# Zigbee32Bridge.net
KiCad netlist of a schematic drawn in Altium Designer
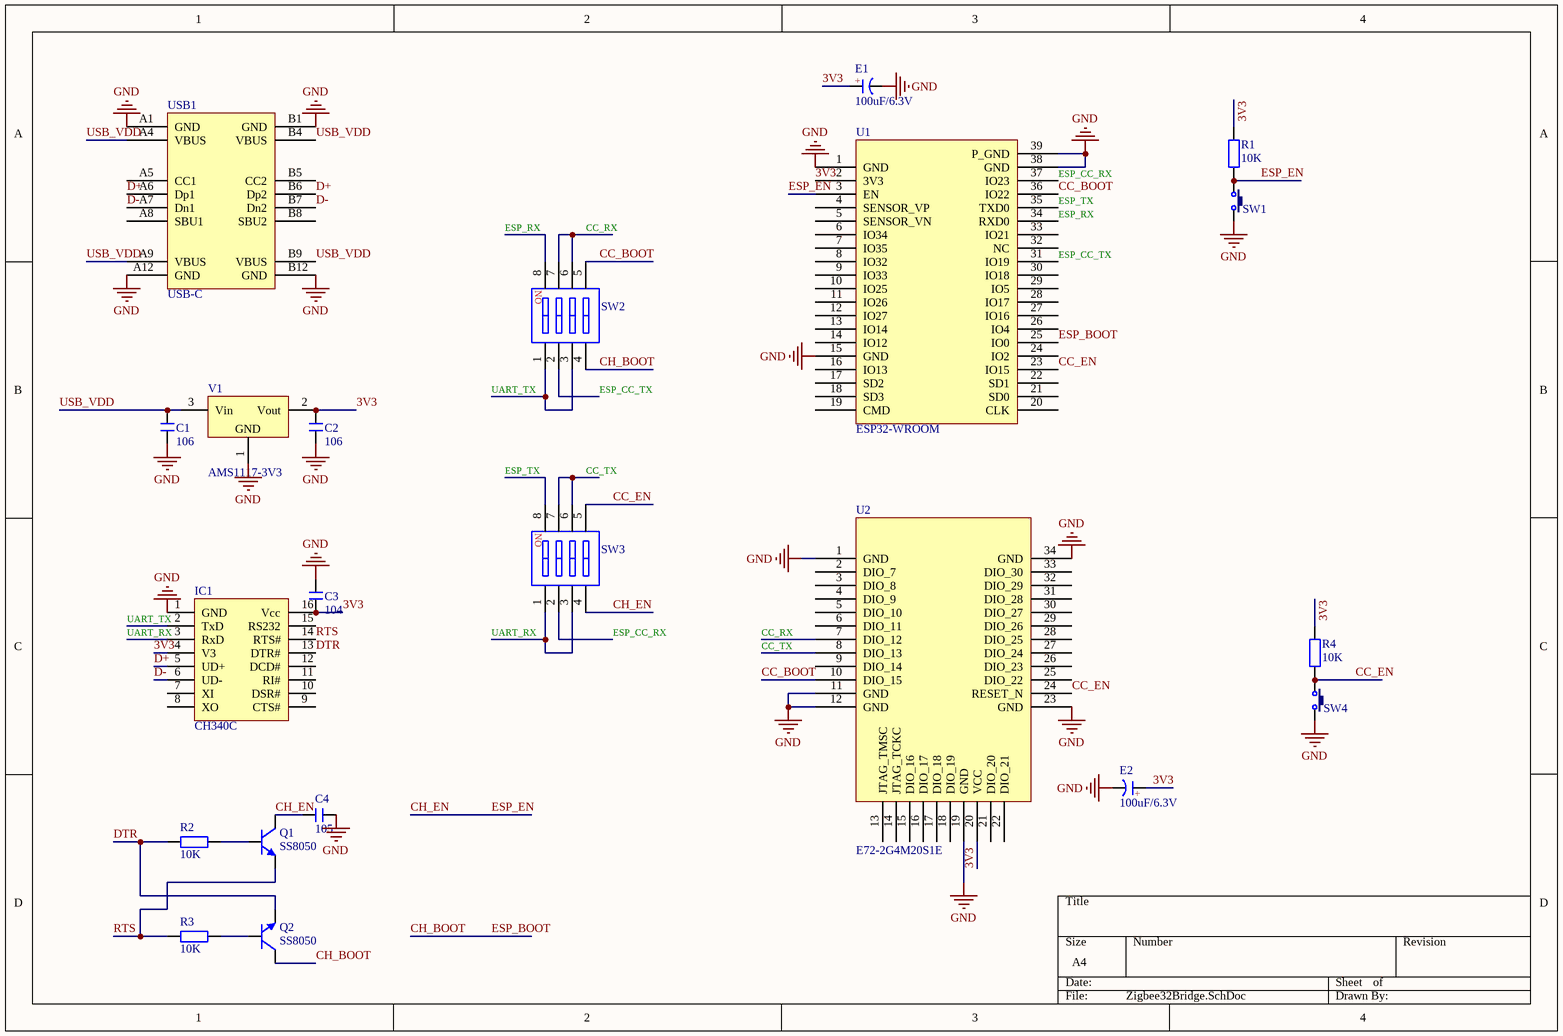
[diagram p0: Zigbee32Bridge.SchDoc]

(export (version "E")
  (design (tool "Eeschema 10.0.6"))
  (components
    (comp (ref "C1")
      (value "106")
      (footprint "C 0603_L")
      (description "无极性贴片电容")
      (fields (field (name "版权归属") "源创客"))
      (libsource (lib "3.1   - 电阻-电容-电感") (part "C"))
    )
    (comp (ref "C2")
      (value "106")
      (footprint "C 0603_L")
      (description "无极性贴片电容")
      (fields (field (name "版权归属") "源创客"))
      (libsource (lib "3.1   - 电阻-电容-电感") (part "C"))
    )
    (comp (ref "C3")
      (value "104")
      (footprint "C 0603_L")
      (description "无极性贴片电容")
      (fields (field (name "版权归属") "源创客"))
      (libsource (lib "3.1   - 电阻-电容-电感") (part "C"))
    )
    (comp (ref "C4")
      (value "105")
      (footprint "C 0603_L")
      (description "无极性贴片电容")
      (fields (field (name "版权归属") "源创客"))
      (libsource (lib "3.1   - 电阻-电容-电感") (part "C"))
    )
    (comp (ref "E1")
      (value "100uF/6.3V")
      (footprint "CD A(3216)")
      (description "贴片钽电容")
      (fields (field (name "版权归属") "源创客"))
      (libsource (lib "3.1   - 电阻-电容-电感") (part "C-CD"))
    )
    (comp (ref "E2")
      (value "100uF/6.3V")
      (footprint "CD A(3216)")
      (description "贴片钽电容")
      (fields (field (name "版权归属") "源创客"))
      (libsource (lib "3.1   - 电阻-电容-电感") (part "C-CD"))
    )
    (comp (ref "IC1")
      (value "CH340C")
      (footprint "SOP16_N")
      (description "串口转USB")
      (fields (field (name "版权归属") "源创客"))
      (libsource (lib "1.1   - IC芯片") (part "CH340G"))
    )
    (comp (ref "Q1")
      (value "SS8050")
      (footprint "SOT23-3N")
      (description "高频放大-NPN型")
      (fields (field (name "版权归属") "源创客"))
      (libsource (lib "6.2   - 三极管") (part "8050-SMD"))
    )
    (comp (ref "Q2")
      (value "SS8050")
      (footprint "SOT23-3N")
      (description "高频放大-NPN型")
      (fields (field (name "版权归属") "源创客"))
      (libsource (lib "6.2   - 三极管") (part "8050-SMD"))
    )
    (comp (ref "R1")
      (value "10K")
      (footprint "R 0603_L")
      (description "贴片电阻")
      (fields (field (name "版权归属") "源创客"))
      (libsource (lib "3.1   - 电阻-电容-电感") (part "R"))
    )
    (comp (ref "R2")
      (value "10K")
      (footprint "R 0603_L")
      (description "贴片电阻")
      (fields (field (name "版权归属") "源创客"))
      (libsource (lib "3.1   - 电阻-电容-电感") (part "R"))
    )
    (comp (ref "R3")
      (value "10K")
      (footprint "R 0603_L")
      (description "贴片电阻")
      (fields (field (name "版权归属") "源创客"))
      (libsource (lib "3.1   - 电阻-电容-电感") (part "R"))
    )
    (comp (ref "R4")
      (value "10K")
      (footprint "R 0603_L")
      (description "贴片电阻")
      (fields (field (name "版权归属") "源创客"))
      (libsource (lib "3.1   - 电阻-电容-电感") (part "R"))
    )
    (comp (ref "SW1")
      (value "3x4x5")
      (footprint "TS3x4x2")
      (description "3x4轻触开关")
      (fields (field (name "版权归属") "源创客"))
      (libsource (lib "5.1   - 按键-开关") (part "TS 3x4"))
    )
    (comp (ref "SW2")
      (value "CSW-4P")
      (footprint "CSW1.27 SMD-4P")
      (description "4路编码开关")
      (fields (field (name "版权归属") "源创客"))
      (libsource (lib "5.1   - 按键-开关") (part "CSW-4P"))
    )
    (comp (ref "SW3")
      (value "CSW-4P")
      (footprint "CSW1.27 SMD-4P")
      (description "4路编码开关")
      (fields (field (name "版权归属") "源创客"))
      (libsource (lib "5.1   - 按键-开关") (part "CSW-4P"))
    )
    (comp (ref "SW4")
      (value "3x4x5")
      (footprint "TS3x4x2")
      (description "3x4轻触开关")
      (fields (field (name "版权归属") "源创客"))
      (libsource (lib "5.1   - 按键-开关") (part "TS 3x4"))
    )
    (comp (ref "U1")
      (value "ESP32-WROOM")
      (footprint "ESP32-WROOM")
      (libsource (lib "15.1 - 未分类器件") (part "ESP32-WROOM"))
    )
    (comp (ref "U2")
      (value "E72-2G4M20S1E")
      (footprint "RF-BM-2652P2")
      (libsource (lib "CustomLib") (part "E72-2G4M20S1E"))
    )
    (comp (ref "USB1")
      (value "USB-C")
      (footprint "USB Type-C-16Pin_A")
      (description "USB-C型母接口")
      (fields (field (name "版权归属") "源创客"))
      (libsource (lib "4.1   - 接口类") (part "USB-C-16P"))
    )
    (comp (ref "V1")
      (value "AMS1117-3V3")
      (footprint "SOT223_N")
      (description "三端稳压芯片")
      (fields (field (name "版权归属") "源创客"))
      (libsource (lib "1.3   - 电源类芯片") (part "AMS1117"))
    )
  )
  (nets
    (net (code "1") (name "/3V3") (class "Default")
      (node (ref "C2") (pin "2") (pinfunction "2_2") (pintype "passive"))
      (node (ref "C3") (pin "2") (pinfunction "2_2") (pintype "passive"))
      (node (ref "E1") (pin "1") (pinfunction "A_1") (pintype "passive"))
      (node (ref "E2") (pin "1") (pinfunction "A_1") (pintype "passive"))
      (node (ref "IC1") (pin "16") (pinfunction "Vcc_16") (pintype "passive"))
      (node (ref "IC1") (pin "4") (pinfunction "V3_4") (pintype "passive"))
      (node (ref "R1") (pin "2") (pinfunction "2_2") (pintype "passive"))
      (node (ref "R4") (pin "2") (pinfunction "2_2") (pintype "passive"))
      (node (ref "U1") (pin "2") (pinfunction "3V3_2") (pintype "passive"))
      (node (ref "U2") (pin "20") (pinfunction "VCC_20") (pintype "passive"))
      (node (ref "V1") (pin "2") (pinfunction "Vout_2") (pintype "passive"))
    )
    (net (code "2") (name "/CC_BOOT") (class "Default")
      (node (ref "SW2") (pin "5") (pinfunction "5_5") (pintype "passive"))
      (node (ref "U1") (pin "36") (pinfunction "IO22_36") (pintype "passive"))
      (node (ref "U2") (pin "10") (pinfunction "DIO_15_10") (pintype "passive"))
    )
    (net (code "3") (name "/CC_EN") (class "Default")
      (node (ref "R4") (pin "1") (pinfunction "1_1") (pintype "passive"))
      (node (ref "SW3") (pin "5") (pinfunction "5_5") (pintype "passive"))
      (node (ref "SW4") (pin "1") (pinfunction "1_1") (pintype "passive"))
      (node (ref "U1") (pin "23") (pinfunction "IO15_23") (pintype "passive"))
      (node (ref "U2") (pin "24") (pinfunction "RESET_N_24") (pintype "passive"))
    )
    (net (code "4") (name "/CC_RX") (class "Default")
      (node (ref "SW2") (pin "6") (pinfunction "6_6") (pintype "passive"))
      (node (ref "SW2") (pin "7") (pinfunction "7_7") (pintype "passive"))
      (node (ref "U2") (pin "7") (pinfunction "DIO_12_7") (pintype "passive"))
    )
    (net (code "5") (name "/CC_TX") (class "Default")
      (node (ref "SW3") (pin "6") (pinfunction "6_6") (pintype "passive"))
      (node (ref "SW3") (pin "7") (pinfunction "7_7") (pintype "passive"))
      (node (ref "U2") (pin "8") (pinfunction "DIO_13_8") (pintype "passive"))
    )
    (net (code "6") (name "/CH_BOOT") (class "Default")
      (node (ref "Q2") (pin "3") (pinfunction "C_3") (pintype "passive"))
      (node (ref "SW2") (pin "4") (pinfunction "4_4") (pintype "passive"))
      (node (ref "U1") (pin "25") (pinfunction "IO0_25") (pintype "passive"))
    )
    (net (code "7") (name "/CH_EN") (class "Default")
      (node (ref "C4") (pin "2") (pinfunction "2_2") (pintype "passive"))
      (node (ref "Q1") (pin "3") (pinfunction "C_3") (pintype "passive"))
      (node (ref "R1") (pin "1") (pinfunction "1_1") (pintype "passive"))
      (node (ref "SW1") (pin "1") (pinfunction "1_1") (pintype "passive"))
      (node (ref "SW3") (pin "4") (pinfunction "4_4") (pintype "passive"))
      (node (ref "U1") (pin "3") (pinfunction "EN_3") (pintype "passive"))
    )
    (net (code "8") (name "/D+") (class "Default")
      (node (ref "IC1") (pin "5") (pinfunction "UD+_5") (pintype "passive"))
      (node (ref "USB1") (pin "A6") (pinfunction "Dp1_A6") (pintype "passive"))
      (node (ref "USB1") (pin "B6") (pinfunction "Dp2_B6") (pintype "passive"))
    )
    (net (code "9") (name "/D-") (class "Default")
      (node (ref "IC1") (pin "6") (pinfunction "UD-_6") (pintype "passive"))
      (node (ref "USB1") (pin "A7") (pinfunction "Dn1_A7") (pintype "passive"))
      (node (ref "USB1") (pin "B7") (pinfunction "Dn2_B7") (pintype "passive"))
    )
    (net (code "10") (name "/DTR") (class "Default")
      (node (ref "IC1") (pin "13") (pinfunction "DTR#_13") (pintype "passive"))
      (node (ref "Q2") (pin "2") (pinfunction "E_2") (pintype "passive"))
      (node (ref "R2") (pin "1") (pinfunction "1_1") (pintype "passive"))
    )
    (net (code "11") (name "/ESP_CC_RX") (class "Default")
      (node (ref "SW3") (pin "2") (pinfunction "2_2") (pintype "passive"))
      (node (ref "U1") (pin "37") (pinfunction "IO23_37") (pintype "passive"))
    )
    (net (code "12") (name "/ESP_CC_TX") (class "Default")
      (node (ref "SW2") (pin "2") (pinfunction "2_2") (pintype "passive"))
      (node (ref "U1") (pin "31") (pinfunction "IO19_31") (pintype "passive"))
    )
    (net (code "13") (name "/ESP_RX") (class "Default")
      (node (ref "SW2") (pin "8") (pinfunction "8_8") (pintype "passive"))
      (node (ref "U1") (pin "34") (pinfunction "RXD0_34") (pintype "passive"))
    )
    (net (code "14") (name "/ESP_TX") (class "Default")
      (node (ref "SW3") (pin "8") (pinfunction "8_8") (pintype "passive"))
      (node (ref "U1") (pin "35") (pinfunction "TXD0_35") (pintype "passive"))
    )
    (net (code "15") (name "/RTS") (class "Default")
      (node (ref "IC1") (pin "14") (pinfunction "RTS#_14") (pintype "passive"))
      (node (ref "Q1") (pin "2") (pinfunction "E_2") (pintype "passive"))
      (node (ref "R3") (pin "1") (pinfunction "1_1") (pintype "passive"))
    )
    (net (code "16") (name "/UART_RX") (class "Default")
      (node (ref "IC1") (pin "3") (pinfunction "RxD_3") (pintype "passive"))
      (node (ref "SW3") (pin "1") (pinfunction "1_1") (pintype "passive"))
      (node (ref "SW3") (pin "3") (pinfunction "3_3") (pintype "passive"))
    )
    (net (code "17") (name "/UART_TX") (class "Default")
      (node (ref "IC1") (pin "2") (pinfunction "TxD_2") (pintype "passive"))
      (node (ref "SW2") (pin "1") (pinfunction "1_1") (pintype "passive"))
      (node (ref "SW2") (pin "3") (pinfunction "3_3") (pintype "passive"))
    )
    (net (code "18") (name "/USB_VDD") (class "Default")
      (node (ref "C1") (pin "2") (pinfunction "2_2") (pintype "passive"))
      (node (ref "USB1") (pin "A4") (pinfunction "VBUS_A4") (pintype "passive"))
      (node (ref "USB1") (pin "A9") (pinfunction "VBUS_A9") (pintype "passive"))
      (node (ref "USB1") (pin "B4") (pinfunction "VBUS_B4") (pintype "passive"))
      (node (ref "USB1") (pin "B9") (pinfunction "VBUS_B9") (pintype "passive"))
      (node (ref "V1") (pin "3") (pinfunction "Vin_3") (pintype "passive"))
    )
    (net (code "19") (name "GND") (class "Default")
      (node (ref "C1") (pin "1") (pinfunction "1_1") (pintype "passive"))
      (node (ref "C2") (pin "1") (pinfunction "1_1") (pintype "passive"))
      (node (ref "C3") (pin "1") (pinfunction "1_1") (pintype "passive"))
      (node (ref "C4") (pin "1") (pinfunction "1_1") (pintype "passive"))
      (node (ref "E1") (pin "2") (pinfunction "K_2") (pintype "passive"))
      (node (ref "E2") (pin "2") (pinfunction "K_2") (pintype "passive"))
      (node (ref "IC1") (pin "1") (pinfunction "GND_1") (pintype "passive"))
      (node (ref "SW1") (pin "2") (pinfunction "2_2") (pintype "passive"))
      (node (ref "SW4") (pin "2") (pinfunction "2_2") (pintype "passive"))
      (node (ref "U1") (pin "1") (pinfunction "GND_1") (pintype "passive"))
      (node (ref "U1") (pin "15") (pinfunction "GND_15") (pintype "passive"))
      (node (ref "U1") (pin "38") (pinfunction "GND_38") (pintype "passive"))
      (node (ref "U1") (pin "39") (pinfunction "P_GND_39") (pintype "passive"))
      (node (ref "U2") (pin "1") (pinfunction "GND_1") (pintype "passive"))
      (node (ref "U2") (pin "11") (pinfunction "GND_11") (pintype "passive"))
      (node (ref "U2") (pin "12") (pinfunction "GND_12") (pintype "passive"))
      (node (ref "U2") (pin "19") (pinfunction "GND_19") (pintype "passive"))
      (node (ref "U2") (pin "23") (pinfunction "GND_23") (pintype "passive"))
      (node (ref "U2") (pin "34") (pinfunction "GND_34") (pintype "passive"))
      (node (ref "USB1") (pin "A1") (pinfunction "GND_A1") (pintype "passive"))
      (node (ref "USB1") (pin "A12") (pinfunction "GND_A12") (pintype "passive"))
      (node (ref "USB1") (pin "B1") (pinfunction "GND_B1") (pintype "passive"))
      (node (ref "USB1") (pin "B12") (pinfunction "GND_B12") (pintype "passive"))
      (node (ref "V1") (pin "1") (pinfunction "GND_1") (pintype "passive"))
    )
    (net (code "20") (name "Net-(Q1-B)") (class "Default")
      (node (ref "Q1") (pin "1") (pinfunction "B_1") (pintype "passive"))
      (node (ref "R2") (pin "2") (pinfunction "2_2") (pintype "passive"))
    )
    (net (code "21") (name "Net-(Q2-B)") (class "Default")
      (node (ref "Q2") (pin "1") (pinfunction "B_1") (pintype "passive"))
      (node (ref "R3") (pin "2") (pinfunction "2_2") (pintype "passive"))
    )
    (net (code "22") (name "unconnected-(IC1-CTS#-Pad9)") (class "Default")
      (node (ref "IC1") (pin "9") (pinfunction "CTS#_9") (pintype "passive"))
    )
    (net (code "23") (name "unconnected-(IC1-DCD#-Pad12)") (class "Default")
      (node (ref "IC1") (pin "12") (pinfunction "DCD#_12") (pintype "passive"))
    )
    (net (code "24") (name "unconnected-(IC1-DSR#-Pad10)") (class "Default")
      (node (ref "IC1") (pin "10") (pinfunction "DSR#_10") (pintype "passive"))
    )
    (net (code "25") (name "unconnected-(IC1-RI#-Pad11)") (class "Default")
      (node (ref "IC1") (pin "11") (pinfunction "RI#_11") (pintype "passive"))
    )
    (net (code "26") (name "unconnected-(IC1-RS232-Pad15)") (class "Default")
      (node (ref "IC1") (pin "15") (pinfunction "RS232_15") (pintype "passive"))
    )
    (net (code "27") (name "unconnected-(IC1-XI-Pad7)") (class "Default")
      (node (ref "IC1") (pin "7") (pinfunction "XI_7") (pintype "passive"))
    )
    (net (code "28") (name "unconnected-(IC1-XO-Pad8)") (class "Default")
      (node (ref "IC1") (pin "8") (pinfunction "XO_8") (pintype "passive"))
    )
    (net (code "29") (name "unconnected-(U1-CLK-Pad20)") (class "Default")
      (node (ref "U1") (pin "20") (pinfunction "CLK_20") (pintype "passive"))
    )
    (net (code "30") (name "unconnected-(U1-CMD-Pad19)") (class "Default")
      (node (ref "U1") (pin "19") (pinfunction "CMD_19") (pintype "passive"))
    )
    (net (code "31") (name "unconnected-(U1-IO2-Pad24)") (class "Default")
      (node (ref "U1") (pin "24") (pinfunction "IO2_24") (pintype "passive"))
    )
    (net (code "32") (name "unconnected-(U1-IO4-Pad26)") (class "Default")
      (node (ref "U1") (pin "26") (pinfunction "IO4_26") (pintype "passive"))
    )
    (net (code "33") (name "unconnected-(U1-IO5-Pad29)") (class "Default")
      (node (ref "U1") (pin "29") (pinfunction "IO5_29") (pintype "passive"))
    )
    (net (code "34") (name "unconnected-(U1-IO12-Pad14)") (class "Default")
      (node (ref "U1") (pin "14") (pinfunction "IO12_14") (pintype "passive"))
    )
    (net (code "35") (name "unconnected-(U1-IO13-Pad16)") (class "Default")
      (node (ref "U1") (pin "16") (pinfunction "IO13_16") (pintype "passive"))
    )
    (net (code "36") (name "unconnected-(U1-IO14-Pad13)") (class "Default")
      (node (ref "U1") (pin "13") (pinfunction "IO14_13") (pintype "passive"))
    )
    (net (code "37") (name "unconnected-(U1-IO16-Pad27)") (class "Default")
      (node (ref "U1") (pin "27") (pinfunction "IO16_27") (pintype "passive"))
    )
    (net (code "38") (name "unconnected-(U1-IO17-Pad28)") (class "Default")
      (node (ref "U1") (pin "28") (pinfunction "IO17_28") (pintype "passive"))
    )
    (net (code "39") (name "unconnected-(U1-IO18-Pad30)") (class "Default")
      (node (ref "U1") (pin "30") (pinfunction "IO18_30") (pintype "passive"))
    )
    (net (code "40") (name "unconnected-(U1-IO21-Pad33)") (class "Default")
      (node (ref "U1") (pin "33") (pinfunction "IO21_33") (pintype "passive"))
    )
    (net (code "41") (name "unconnected-(U1-IO25-Pad10)") (class "Default")
      (node (ref "U1") (pin "10") (pinfunction "IO25_10") (pintype "passive"))
    )
    (net (code "42") (name "unconnected-(U1-IO26-Pad11)") (class "Default")
      (node (ref "U1") (pin "11") (pinfunction "IO26_11") (pintype "passive"))
    )
    (net (code "43") (name "unconnected-(U1-IO27-Pad12)") (class "Default")
      (node (ref "U1") (pin "12") (pinfunction "IO27_12") (pintype "passive"))
    )
    (net (code "44") (name "unconnected-(U1-IO32-Pad8)") (class "Default")
      (node (ref "U1") (pin "8") (pinfunction "IO32_8") (pintype "passive"))
    )
    (net (code "45") (name "unconnected-(U1-IO33-Pad9)") (class "Default")
      (node (ref "U1") (pin "9") (pinfunction "IO33_9") (pintype "passive"))
    )
    (net (code "46") (name "unconnected-(U1-IO34-Pad6)") (class "Default")
      (node (ref "U1") (pin "6") (pinfunction "IO34_6") (pintype "passive"))
    )
    (net (code "47") (name "unconnected-(U1-IO35-Pad7)") (class "Default")
      (node (ref "U1") (pin "7") (pinfunction "IO35_7") (pintype "passive"))
    )
    (net (code "48") (name "unconnected-(U1-NC-Pad32)") (class "Default")
      (node (ref "U1") (pin "32") (pinfunction "NC_32") (pintype "passive"))
    )
    (net (code "49") (name "unconnected-(U1-SD0-Pad21)") (class "Default")
      (node (ref "U1") (pin "21") (pinfunction "SD0_21") (pintype "passive"))
    )
    (net (code "50") (name "unconnected-(U1-SD1-Pad22)") (class "Default")
      (node (ref "U1") (pin "22") (pinfunction "SD1_22") (pintype "passive"))
    )
    (net (code "51") (name "unconnected-(U1-SD2-Pad17)") (class "Default")
      (node (ref "U1") (pin "17") (pinfunction "SD2_17") (pintype "passive"))
    )
    (net (code "52") (name "unconnected-(U1-SD3-Pad18)") (class "Default")
      (node (ref "U1") (pin "18") (pinfunction "SD3_18") (pintype "passive"))
    )
    (net (code "53") (name "unconnected-(U1-SENSOR_VN-Pad5)") (class "Default")
      (node (ref "U1") (pin "5") (pinfunction "SENSOR_VN_5") (pintype "passive"))
    )
    (net (code "54") (name "unconnected-(U1-SENSOR_VP-Pad4)") (class "Default")
      (node (ref "U1") (pin "4") (pinfunction "SENSOR_VP_4") (pintype "passive"))
    )
    (net (code "55") (name "unconnected-(U2-DIO_7-Pad2)") (class "Default")
      (node (ref "U2") (pin "2") (pinfunction "DIO_7_2") (pintype "passive"))
    )
    (net (code "56") (name "unconnected-(U2-DIO_8-Pad3)") (class "Default")
      (node (ref "U2") (pin "3") (pinfunction "DIO_8_3") (pintype "passive"))
    )
    (net (code "57") (name "unconnected-(U2-DIO_9-Pad4)") (class "Default")
      (node (ref "U2") (pin "4") (pinfunction "DIO_9_4") (pintype "passive"))
    )
    (net (code "58") (name "unconnected-(U2-DIO_10-Pad5)") (class "Default")
      (node (ref "U2") (pin "5") (pinfunction "DIO_10_5") (pintype "passive"))
    )
    (net (code "59") (name "unconnected-(U2-DIO_11-Pad6)") (class "Default")
      (node (ref "U2") (pin "6") (pinfunction "DIO_11_6") (pintype "passive"))
    )
    (net (code "60") (name "unconnected-(U2-DIO_14-Pad9)") (class "Default")
      (node (ref "U2") (pin "9") (pinfunction "DIO_14_9") (pintype "passive"))
    )
    (net (code "61") (name "unconnected-(U2-DIO_16-Pad15)") (class "Default")
      (node (ref "U2") (pin "15") (pinfunction "DIO_16_15") (pintype "passive"))
    )
    (net (code "62") (name "unconnected-(U2-DIO_17-Pad16)") (class "Default")
      (node (ref "U2") (pin "16") (pinfunction "DIO_17_16") (pintype "passive"))
    )
    (net (code "63") (name "unconnected-(U2-DIO_18-Pad17)") (class "Default")
      (node (ref "U2") (pin "17") (pinfunction "DIO_18_17") (pintype "passive"))
    )
    (net (code "64") (name "unconnected-(U2-DIO_19-Pad18)") (class "Default")
      (node (ref "U2") (pin "18") (pinfunction "DIO_19_18") (pintype "passive"))
    )
    (net (code "65") (name "unconnected-(U2-DIO_20-Pad21)") (class "Default")
      (node (ref "U2") (pin "21") (pinfunction "DIO_20_21") (pintype "passive"))
    )
    (net (code "66") (name "unconnected-(U2-DIO_21-Pad22)") (class "Default")
      (node (ref "U2") (pin "22") (pinfunction "DIO_21_22") (pintype "passive"))
    )
    (net (code "67") (name "unconnected-(U2-DIO_22-Pad25)") (class "Default")
      (node (ref "U2") (pin "25") (pinfunction "DIO_22_25") (pintype "passive"))
    )
    (net (code "68") (name "unconnected-(U2-DIO_23-Pad26)") (class "Default")
      (node (ref "U2") (pin "26") (pinfunction "DIO_23_26") (pintype "passive"))
    )
    (net (code "69") (name "unconnected-(U2-DIO_24-Pad27)") (class "Default")
      (node (ref "U2") (pin "27") (pinfunction "DIO_24_27") (pintype "passive"))
    )
    (net (code "70") (name "unconnected-(U2-DIO_25-Pad28)") (class "Default")
      (node (ref "U2") (pin "28") (pinfunction "DIO_25_28") (pintype "passive"))
    )
    (net (code "71") (name "unconnected-(U2-DIO_26-Pad29)") (class "Default")
      (node (ref "U2") (pin "29") (pinfunction "DIO_26_29") (pintype "passive"))
    )
    (net (code "72") (name "unconnected-(U2-DIO_27-Pad30)") (class "Default")
      (node (ref "U2") (pin "30") (pinfunction "DIO_27_30") (pintype "passive"))
    )
    (net (code "73") (name "unconnected-(U2-DIO_28-Pad31)") (class "Default")
      (node (ref "U2") (pin "31") (pinfunction "DIO_28_31") (pintype "passive"))
    )
    (net (code "74") (name "unconnected-(U2-DIO_29-Pad32)") (class "Default")
      (node (ref "U2") (pin "32") (pinfunction "DIO_29_32") (pintype "passive"))
    )
    (net (code "75") (name "unconnected-(U2-DIO_30-Pad33)") (class "Default")
      (node (ref "U2") (pin "33") (pinfunction "DIO_30_33") (pintype "passive"))
    )
    (net (code "76") (name "unconnected-(U2-JTAG_TCKC-Pad14)") (class "Default")
      (node (ref "U2") (pin "14") (pinfunction "JTAG_TCKC_14") (pintype "passive"))
    )
    (net (code "77") (name "unconnected-(U2-JTAG_TMSC-Pad13)") (class "Default")
      (node (ref "U2") (pin "13") (pinfunction "JTAG_TMSC_13") (pintype "passive"))
    )
    (net (code "78") (name "unconnected-(USB1-CC1-PadA5)") (class "Default")
      (node (ref "USB1") (pin "A5") (pinfunction "CC1_A5") (pintype "passive"))
    )
    (net (code "79") (name "unconnected-(USB1-CC2-PadB5)") (class "Default")
      (node (ref "USB1") (pin "B5") (pinfunction "CC2_B5") (pintype "passive"))
    )
    (net (code "80") (name "unconnected-(USB1-SBU1-PadA8)") (class "Default")
      (node (ref "USB1") (pin "A8") (pinfunction "SBU1_A8") (pintype "passive"))
    )
    (net (code "81") (name "unconnected-(USB1-SBU2-PadB8)") (class "Default")
      (node (ref "USB1") (pin "B8") (pinfunction "SBU2_B8") (pintype "passive"))
    )
  )
)
